# 24V_to_5V_regulator.net
KiCad netlist of a schematic drawn in Altium Designer
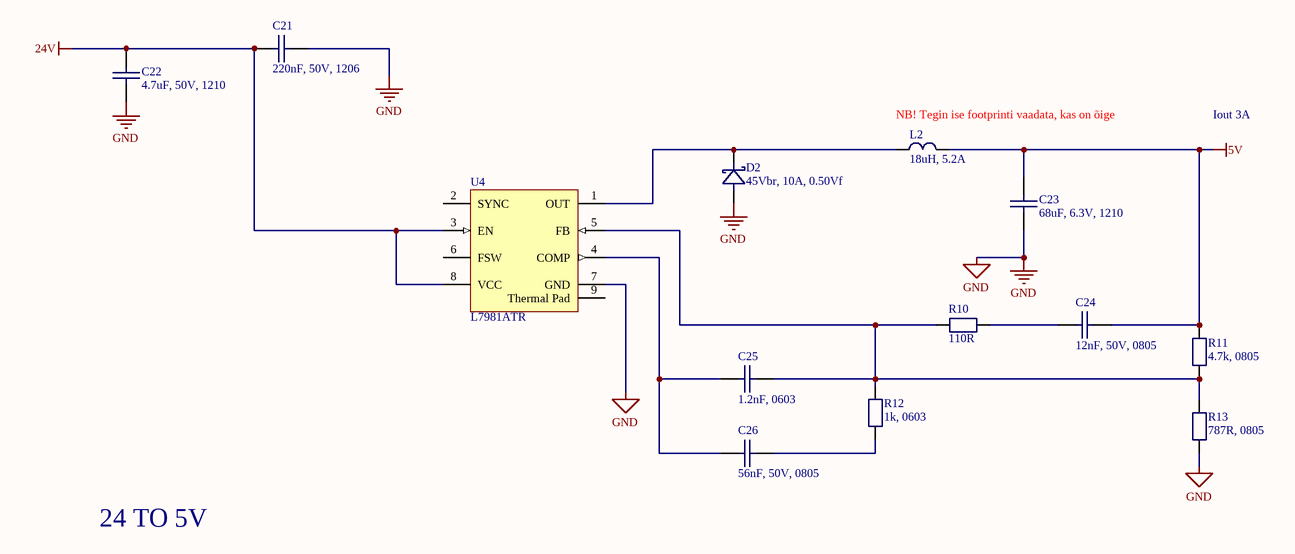
[diagram p0: 24V_to_5V_regulator.SchDoc]

(export (version "E")
  (design (tool "Eeschema 10.0.6"))
  (components
    (comp (ref "C21")
      (value "220nF, 50V, 1206")
      (footprint "3216 [1206] CAP")
      (libsource (lib "AS_component_library") (part "Capacitor"))
    )
    (comp (ref "C22")
      (value "4.7uF, 50V, 1210")
      (footprint "3225 [1210] CAP")
      (libsource (lib "AS_component_library") (part "Capacitor"))
    )
    (comp (ref "C23")
      (value "68uF, 6.3V, 1210")
      (footprint "3225 [1210] CAP")
      (libsource (lib "AS_component_library") (part "Capacitor"))
    )
    (comp (ref "C24")
      (value "12nF, 50V, 0805")
      (footprint "2012 [0805] CAP")
      (libsource (lib "AS_component_library") (part "Capacitor"))
    )
    (comp (ref "C25")
      (value "1.2nF, 0603")
      (footprint "1608 [0603] CAP")
      (libsource (lib "AS_component_library") (part "Capacitor"))
    )
    (comp (ref "C26")
      (value "56nF, 50V, 0805")
      (footprint "2012 [0805] CAP")
      (libsource (lib "AS_component_library") (part "Capacitor"))
    )
    (comp (ref "D2")
      (value "45Vbr, 10A, 0.50Vf")
      (footprint "DPAK (TO252-3)")
      (libsource (lib "AS_component_library") (part "Diode Shottky"))
    )
    (comp (ref "L2")
      (value "18uH, 5.2A")
      (footprint "SRR12xx IND")
      (libsource (lib "AS_component_library") (part "Inductor"))
    )
    (comp (ref "R10")
      (value "110R")
      (footprint "2012 [0805] RES")
      (libsource (lib "AS_component_library") (part "Resistor"))
    )
    (comp (ref "R11")
      (value "4.7k, 0805")
      (footprint "2012 [0805] RES")
      (libsource (lib "AS_component_library") (part "Resistor"))
    )
    (comp (ref "R12")
      (value "1k, 0603")
      (footprint "1608 [0603] RES")
      (libsource (lib "AS_component_library") (part "Resistor"))
    )
    (comp (ref "R13")
      (value "787R, 0805")
      (footprint "2012 [0805] RES")
      (libsource (lib "AS_component_library") (part "Resistor"))
    )
    (comp (ref "U4")
      (value "L7981ATR")
      (footprint "HSOP8-D1_N")
      (description "3 A step-down switching regulator, 8-Pin HSOP, Tape and Reel")
      (libsource (lib "STMicroelectronics Power Management DC-DC Conversion") (part "L7981ATR"))
    )
  )
  (nets
    (net (code "1") (name "5V") (class "Default")
      (node (ref "C23") (pin "1") (pinfunction "1_1") (pintype "passive"))
      (node (ref "C24") (pin "1") (pinfunction "1_1") (pintype "passive"))
      (node (ref "L2") (pin "2") (pinfunction "2_2") (pintype "passive"))
      (node (ref "R11") (pin "2") (pinfunction "2_2") (pintype "passive"))
    )
    (net (code "2") (name "24V") (class "Default")
      (node (ref "C21") (pin "2") (pinfunction "2_2") (pintype "passive"))
      (node (ref "C22") (pin "1") (pinfunction "1_1") (pintype "passive"))
      (node (ref "U4") (pin "3") (pinfunction "EN_3") (pintype "input"))
      (node (ref "U4") (pin "8") (pinfunction "VCC_8") (pintype "power_in"))
    )
    (net (code "3") (name "GND") (class "Default")
      (node (ref "C21") (pin "1") (pinfunction "1_1") (pintype "passive"))
      (node (ref "C22") (pin "2") (pinfunction "2_2") (pintype "passive"))
      (node (ref "C23") (pin "2") (pinfunction "2_2") (pintype "passive"))
      (node (ref "D2") (pin "2") (pinfunction "2_2") (pintype "passive"))
      (node (ref "R13") (pin "1") (pinfunction "1_1") (pintype "passive"))
      (node (ref "U4") (pin "7") (pinfunction "GND_7") (pintype "power_in"))
    )
    (net (code "4") (name "Net-(C24-Pad2)") (class "Default")
      (node (ref "C24") (pin "2") (pinfunction "2_2") (pintype "passive"))
      (node (ref "R10") (pin "2") (pinfunction "2_2") (pintype "passive"))
    )
    (net (code "5") (name "Net-(C26-Pad1)") (class "Default")
      (node (ref "C26") (pin "1") (pinfunction "1_1") (pintype "passive"))
      (node (ref "R12") (pin "1") (pinfunction "1_1") (pintype "passive"))
    )
    (net (code "6") (name "Net-(U4-COMP)") (class "Default")
      (node (ref "C25") (pin "2") (pinfunction "2_2") (pintype "passive"))
      (node (ref "C26") (pin "2") (pinfunction "2_2") (pintype "passive"))
      (node (ref "U4") (pin "4") (pinfunction "COMP_4") (pintype "output"))
    )
    (net (code "7") (name "Net-(U4-FB)") (class "Default")
      (node (ref "C25") (pin "1") (pinfunction "1_1") (pintype "passive"))
      (node (ref "R10") (pin "1") (pinfunction "1_1") (pintype "passive"))
      (node (ref "R11") (pin "1") (pinfunction "1_1") (pintype "passive"))
      (node (ref "R12") (pin "2") (pinfunction "2_2") (pintype "passive"))
      (node (ref "R13") (pin "2") (pinfunction "2_2") (pintype "passive"))
      (node (ref "U4") (pin "5") (pinfunction "FB_5") (pintype "input"))
    )
    (net (code "8") (name "Net-(U4-OUT)") (class "Default")
      (node (ref "D2") (pin "1") (pinfunction "1_1") (pintype "passive"))
      (node (ref "L2") (pin "1") (pinfunction "1_1") (pintype "passive"))
      (node (ref "U4") (pin "1") (pinfunction "OUT_1") (pintype "power_in"))
    )
    (net (code "9") (name "unconnected-(U4-FSW-Pad6)") (class "Default")
      (node (ref "U4") (pin "6") (pinfunction "FSW_6") (pintype "passive"))
    )
    (net (code "10") (name "unconnected-(U4-SYNC-Pad2)") (class "Default")
      (node (ref "U4") (pin "2") (pinfunction "SYNC_2") (pintype "passive"))
    )
    (net (code "11") (name "unconnected-(U4-Thermal_Pad-Pad9)") (class "Default")
      (node (ref "U4") (pin "9") (pinfunction "Thermal_Pad_9") (pintype "power_in"))
    )
  )
)
